# caldi.net
KiCad netlist of a schematic drawn in EAGLE
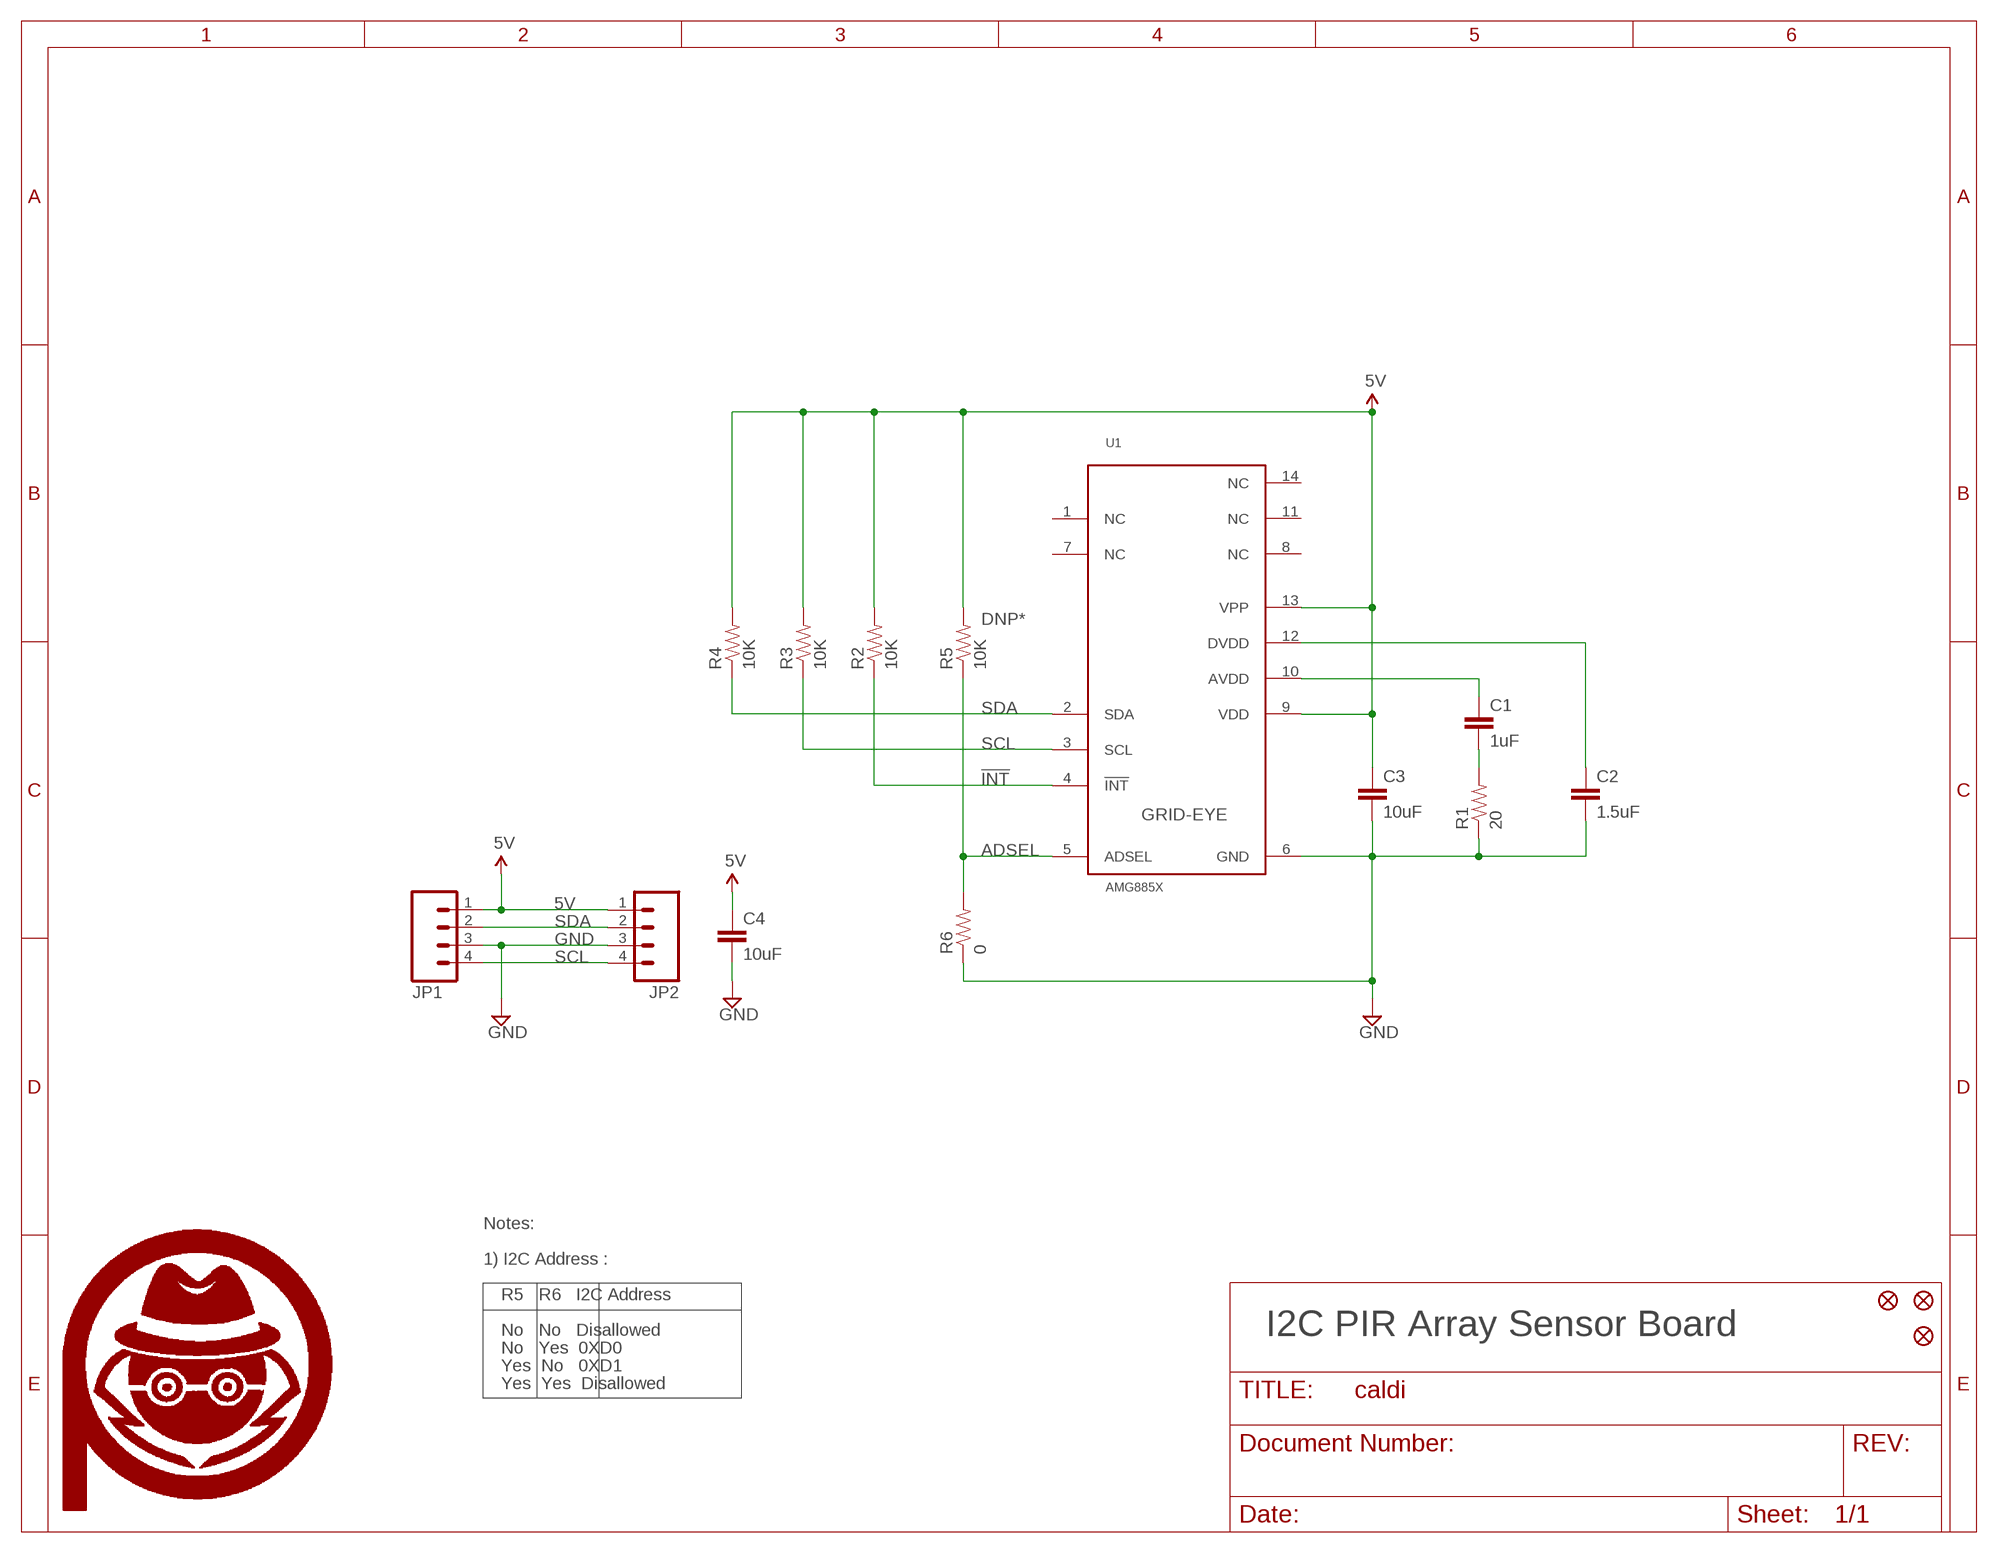
[diagram p0: schematic, sheet 1]

(export (version "E")
  (design (tool "Eeschema 10.0.6"))
  (components
    (comp (ref "C1")
      (value "1uF")
      (footprint "eagle-import:0603-CAP")
      (libsource (lib "eagle-import") (part "CAP0603-CAP"))
    )
    (comp (ref "C2")
      (value "1.5uF")
      (footprint "eagle-import:0603-CAP")
      (libsource (lib "eagle-import") (part "CAP0603-CAP"))
    )
    (comp (ref "C3")
      (value "10uF")
      (footprint "eagle-import:0603-CAP")
      (libsource (lib "eagle-import") (part "CAP0603-CAP"))
    )
    (comp (ref "C4")
      (value "10uF")
      (footprint "eagle-import:0603-CAP")
      (libsource (lib "eagle-import") (part "CAP0603-CAP"))
    )
    (comp (ref "JP1")
      (value "M04POLAR_LOCK")
      (footprint "eagle-import:MOLEX-1X4_LOCK")
      (libsource (lib "eagle-import") (part "M04POLAR_LOCK"))
    )
    (comp (ref "JP2")
      (value "M04POLAR_LOCK")
      (footprint "eagle-import:MOLEX-1X4_LOCK")
      (libsource (lib "eagle-import") (part "M04POLAR_LOCK"))
    )
    (comp (ref "JP3")
      (value "FIDUCIAL1X2")
      (footprint "eagle-import:FIDUCIAL-1X2")
      (libsource (lib "eagle-import") (part "FIDUCIAL1X2"))
    )
    (comp (ref "JP4")
      (value "FIDUCIAL1X2")
      (footprint "eagle-import:FIDUCIAL-1X2")
      (libsource (lib "eagle-import") (part "FIDUCIAL1X2"))
    )
    (comp (ref "JP5")
      (value "FIDUCIAL1X2")
      (footprint "eagle-import:FIDUCIAL-1X2")
      (libsource (lib "eagle-import") (part "FIDUCIAL1X2"))
    )
    (comp (ref "R1")
      (value "20")
      (footprint "eagle-import:0603-RES")
      (libsource (lib "eagle-import") (part "RESISTOR_SFE0603-RES"))
    )
    (comp (ref "R2")
      (value "10K")
      (footprint "eagle-import:0603-RES")
      (libsource (lib "eagle-import") (part "RESISTOR_SFE0603-RES"))
    )
    (comp (ref "R3")
      (value "10K")
      (footprint "eagle-import:0603-RES")
      (libsource (lib "eagle-import") (part "RESISTOR_SFE0603-RES"))
    )
    (comp (ref "R4")
      (value "10K")
      (footprint "eagle-import:0603-RES")
      (libsource (lib "eagle-import") (part "RESISTOR_SFE0603-RES"))
    )
    (comp (ref "R5")
      (value "10K")
      (footprint "eagle-import:0603-RES")
      (libsource (lib "eagle-import") (part "RESISTOR_SFE0603-RES"))
    )
    (comp (ref "R6")
      (value "0")
      (footprint "eagle-import:0603-RES")
      (libsource (lib "eagle-import") (part "RESISTOR_SFE0603-RES"))
    )
    (comp (ref "U$4")
      (value "PA_LOGO_SYMMED")
      (footprint "eagle-import:PA_LOGO_AGENT_MED_SYM")
      (libsource (lib "eagle-import") (part "PA_LOGO_SYMMED"))
    )
    (comp (ref "U1")
      (value "AMG885X")
      (footprint "eagle-import:AMG885X")
      (libsource (lib "eagle-import") (part "AMG885X"))
    )
  )
  (nets
    (net (code "1") (name "/ADSEL") (class "Default")
      (node (ref "R5") (pin "1") (pinfunction "1_1") (pintype "passive"))
      (node (ref "R6") (pin "2") (pinfunction "2_2") (pintype "passive"))
      (node (ref "U1") (pin "5") (pinfunction "ADSEL_5") (pintype "bidirectional"))
    )
    (net (code "2") (name "/SCL") (class "Default")
      (node (ref "JP1") (pin "4") (pinfunction "4_4") (pintype "passive"))
      (node (ref "JP2") (pin "4") (pinfunction "4_4") (pintype "passive"))
      (node (ref "R3") (pin "1") (pinfunction "1_1") (pintype "passive"))
      (node (ref "U1") (pin "3") (pinfunction "SCL_3") (pintype "bidirectional"))
    )
    (net (code "3") (name "/SDA") (class "Default")
      (node (ref "JP1") (pin "2") (pinfunction "2_2") (pintype "passive"))
      (node (ref "JP2") (pin "2") (pinfunction "2_2") (pintype "passive"))
      (node (ref "R4") (pin "1") (pinfunction "1_1") (pintype "passive"))
      (node (ref "U1") (pin "2") (pinfunction "SDA_2") (pintype "bidirectional"))
    )
    (net (code "4") (name "/~{INT}") (class "Default")
      (node (ref "R2") (pin "1") (pinfunction "1_1") (pintype "passive"))
      (node (ref "U1") (pin "4") (pinfunction "~{INT}_4") (pintype "bidirectional"))
    )
    (net (code "5") (name "5V") (class "Default")
      (node (ref "C3") (pin "1") (pinfunction "1_1") (pintype "passive"))
      (node (ref "C4") (pin "1") (pinfunction "1_1") (pintype "passive"))
      (node (ref "JP1") (pin "1") (pinfunction "1_1") (pintype "passive"))
      (node (ref "JP2") (pin "1") (pinfunction "1_1") (pintype "passive"))
      (node (ref "R2") (pin "2") (pinfunction "2_2") (pintype "passive"))
      (node (ref "R3") (pin "2") (pinfunction "2_2") (pintype "passive"))
      (node (ref "R4") (pin "2") (pinfunction "2_2") (pintype "passive"))
      (node (ref "R5") (pin "2") (pinfunction "2_2") (pintype "passive"))
      (node (ref "U1") (pin "13") (pinfunction "VPP_13") (pintype "power_in"))
      (node (ref "U1") (pin "9") (pinfunction "VDD_9") (pintype "power_in"))
    )
    (net (code "6") (name "GND") (class "Default")
      (node (ref "C2") (pin "2") (pinfunction "2_2") (pintype "passive"))
      (node (ref "C3") (pin "2") (pinfunction "2_2") (pintype "passive"))
      (node (ref "C4") (pin "2") (pinfunction "2_2") (pintype "passive"))
      (node (ref "JP1") (pin "3") (pinfunction "3_3") (pintype "passive"))
      (node (ref "JP2") (pin "3") (pinfunction "3_3") (pintype "passive"))
      (node (ref "R1") (pin "1") (pinfunction "1_1") (pintype "passive"))
      (node (ref "R6") (pin "1") (pinfunction "1_1") (pintype "passive"))
      (node (ref "U1") (pin "6") (pinfunction "GND_6") (pintype "power_in"))
    )
    (net (code "7") (name "Net-(C1-Pad2)") (class "Default")
      (node (ref "C1") (pin "2") (pinfunction "2_2") (pintype "passive"))
      (node (ref "R1") (pin "2") (pinfunction "2_2") (pintype "passive"))
    )
    (net (code "8") (name "Net-(U1-AVDD)") (class "Default")
      (node (ref "C1") (pin "1") (pinfunction "1_1") (pintype "passive"))
      (node (ref "U1") (pin "10") (pinfunction "AVDD_10") (pintype "power_in"))
    )
    (net (code "9") (name "Net-(U1-DVDD)") (class "Default")
      (node (ref "C2") (pin "1") (pinfunction "1_1") (pintype "passive"))
      (node (ref "U1") (pin "12") (pinfunction "DVDD_12") (pintype "power_in"))
    )
    (net (code "10") (name "unconnected-(U1-NC-Pad1)") (class "Default")
      (node (ref "U1") (pin "1") (pinfunction "NC_1") (pintype "no_connect"))
    )
    (net (code "11") (name "unconnected-(U1-NC-Pad7)") (class "Default")
      (node (ref "U1") (pin "7") (pinfunction "NC_7") (pintype "no_connect"))
    )
    (net (code "12") (name "unconnected-(U1-NC-Pad8)") (class "Default")
      (node (ref "U1") (pin "8") (pinfunction "NC_8") (pintype "no_connect"))
    )
    (net (code "13") (name "unconnected-(U1-NC-Pad11)") (class "Default")
      (node (ref "U1") (pin "11") (pinfunction "NC_11") (pintype "no_connect"))
    )
    (net (code "14") (name "unconnected-(U1-NC-Pad14)") (class "Default")
      (node (ref "U1") (pin "14") (pinfunction "NC_14") (pintype "no_connect"))
    )
  )
)
